# 100ma.net
KiCad netlist of a schematic drawn in EAGLE
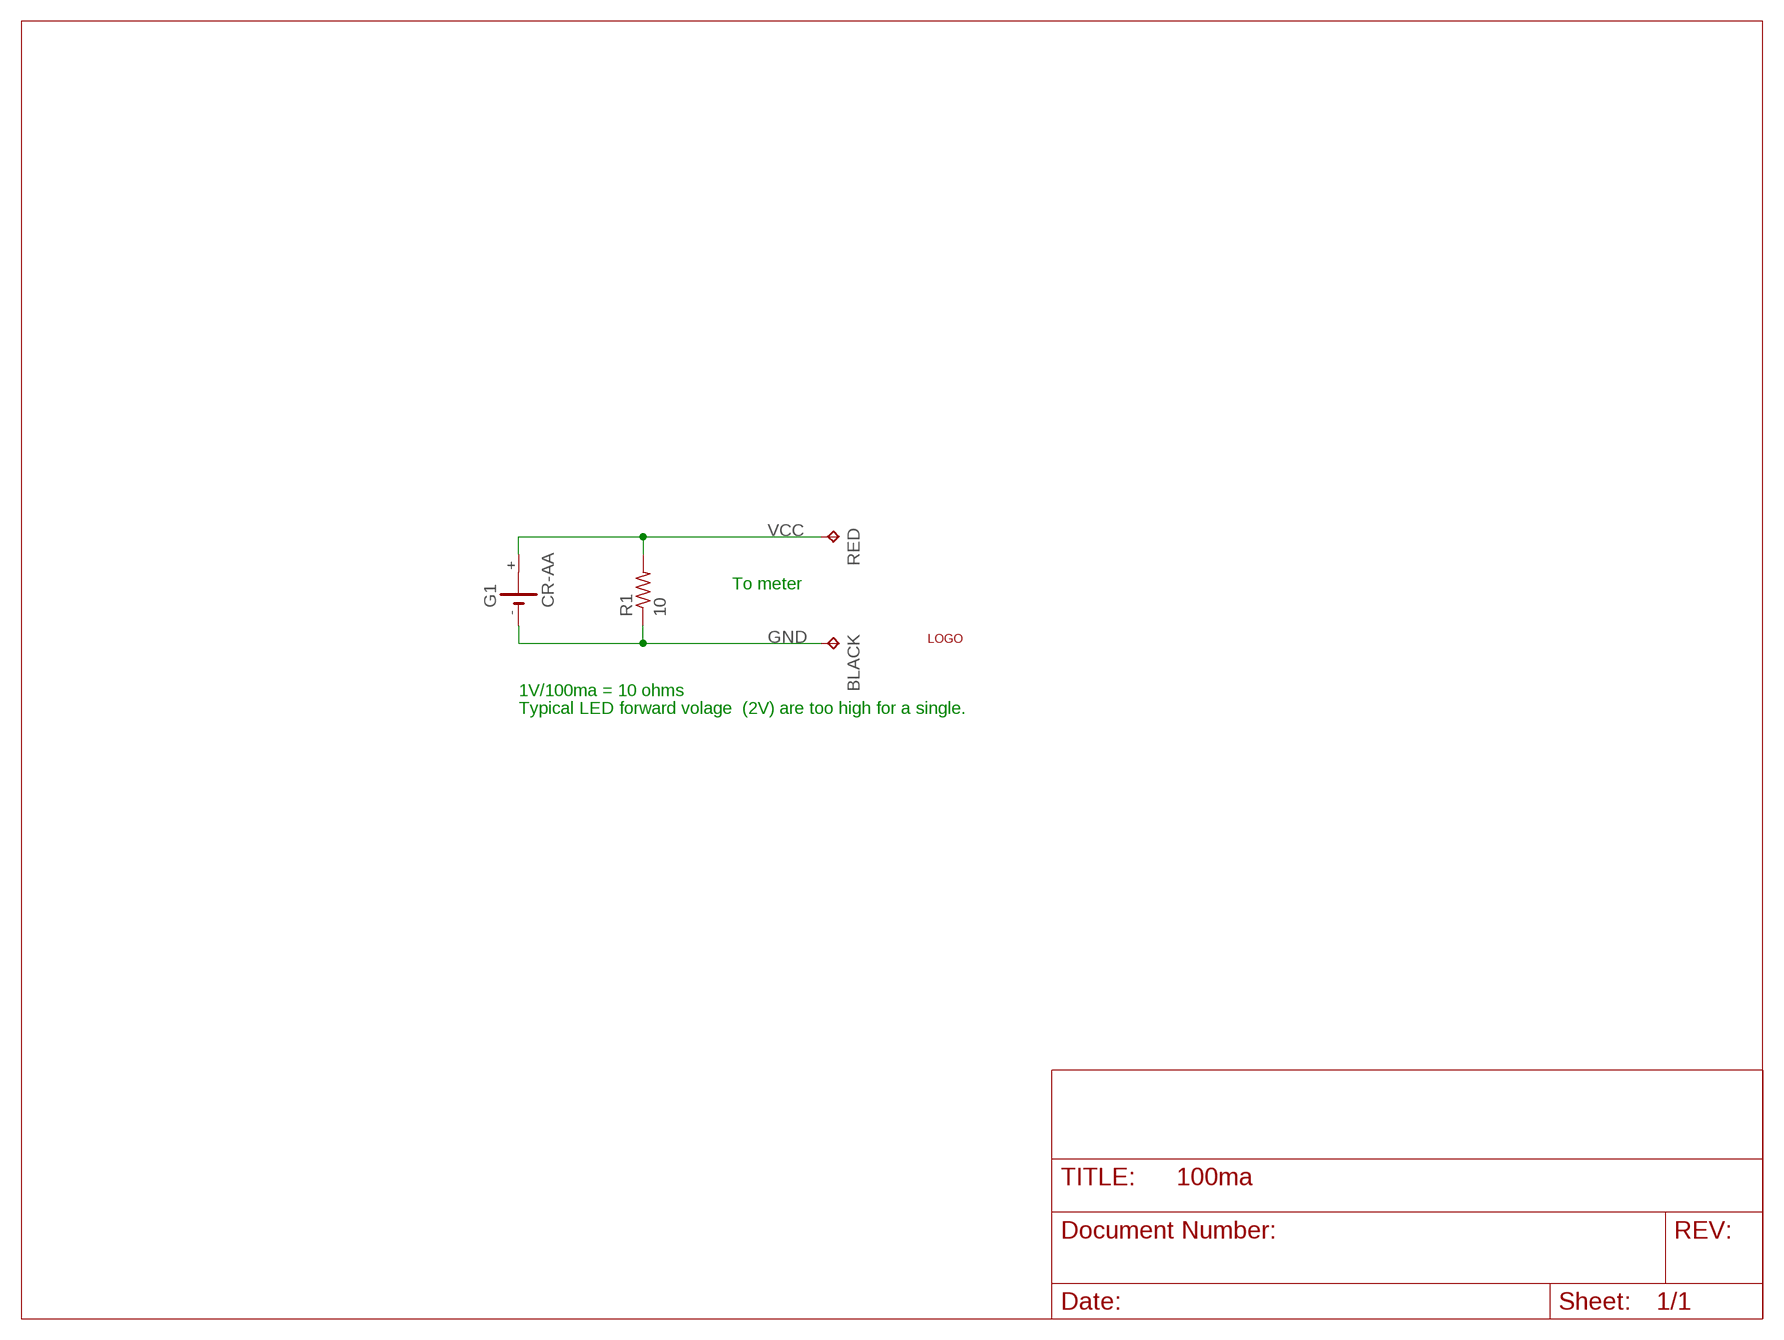
[diagram p0: schematic, sheet 1]

(export (version "E")
  (design (tool "Eeschema 10.0.6"))
  (components
    (comp (ref "BLACK")
      (value "TPB2,54")
      (footprint "eagle-import:B2,54")
      (libsource (lib "eagle-import") (part "TPB2,54"))
    )
    (comp (ref "G1")
      (value "CR-AA")
      (footprint "eagle-import:CRAA")
      (libsource (lib "eagle-import") (part "CR-AA"))
    )
    (comp (ref "LOGO")
      (value "LOGO")
      (footprint "eagle-import:LOGO")
      (libsource (lib "eagle-import") (part "LOGO"))
    )
    (comp (ref "R1")
      (value "10")
      (footprint "eagle-import:0207_10")
      (libsource (lib "eagle-import") (part "R-US_0207/10"))
    )
    (comp (ref "RED")
      (value "TPB2,54")
      (footprint "eagle-import:B2,54")
      (libsource (lib "eagle-import") (part "TPB2,54"))
    )
  )
  (nets
    (net (code "1") (name "/GND") (class "Default")
      (node (ref "BLACK") (pin "TP") (pinfunction "TP_TP") (pintype "input"))
      (node (ref "G1") (pin "-") (pinfunction "-_-") (pintype "passive"))
      (node (ref "R1") (pin "1") (pinfunction "1_1") (pintype "passive"))
    )
    (net (code "2") (name "/VCC") (class "Default")
      (node (ref "G1") (pin "+") (pinfunction "+_+") (pintype "passive"))
      (node (ref "R1") (pin "2") (pinfunction "2_2") (pintype "passive"))
      (node (ref "RED") (pin "TP") (pinfunction "TP_TP") (pintype "input"))
    )
    (net (code "3") (name "unconnected-(G1-+-Pad+@1)") (class "Default")
      (node (ref "G1") (pin "+@1") (pinfunction "+_+@1") (pintype "passive"))
    )
  )
)
